# PCB-ACMSL.net
KiCad netlist of a schematic drawn in EAGLE
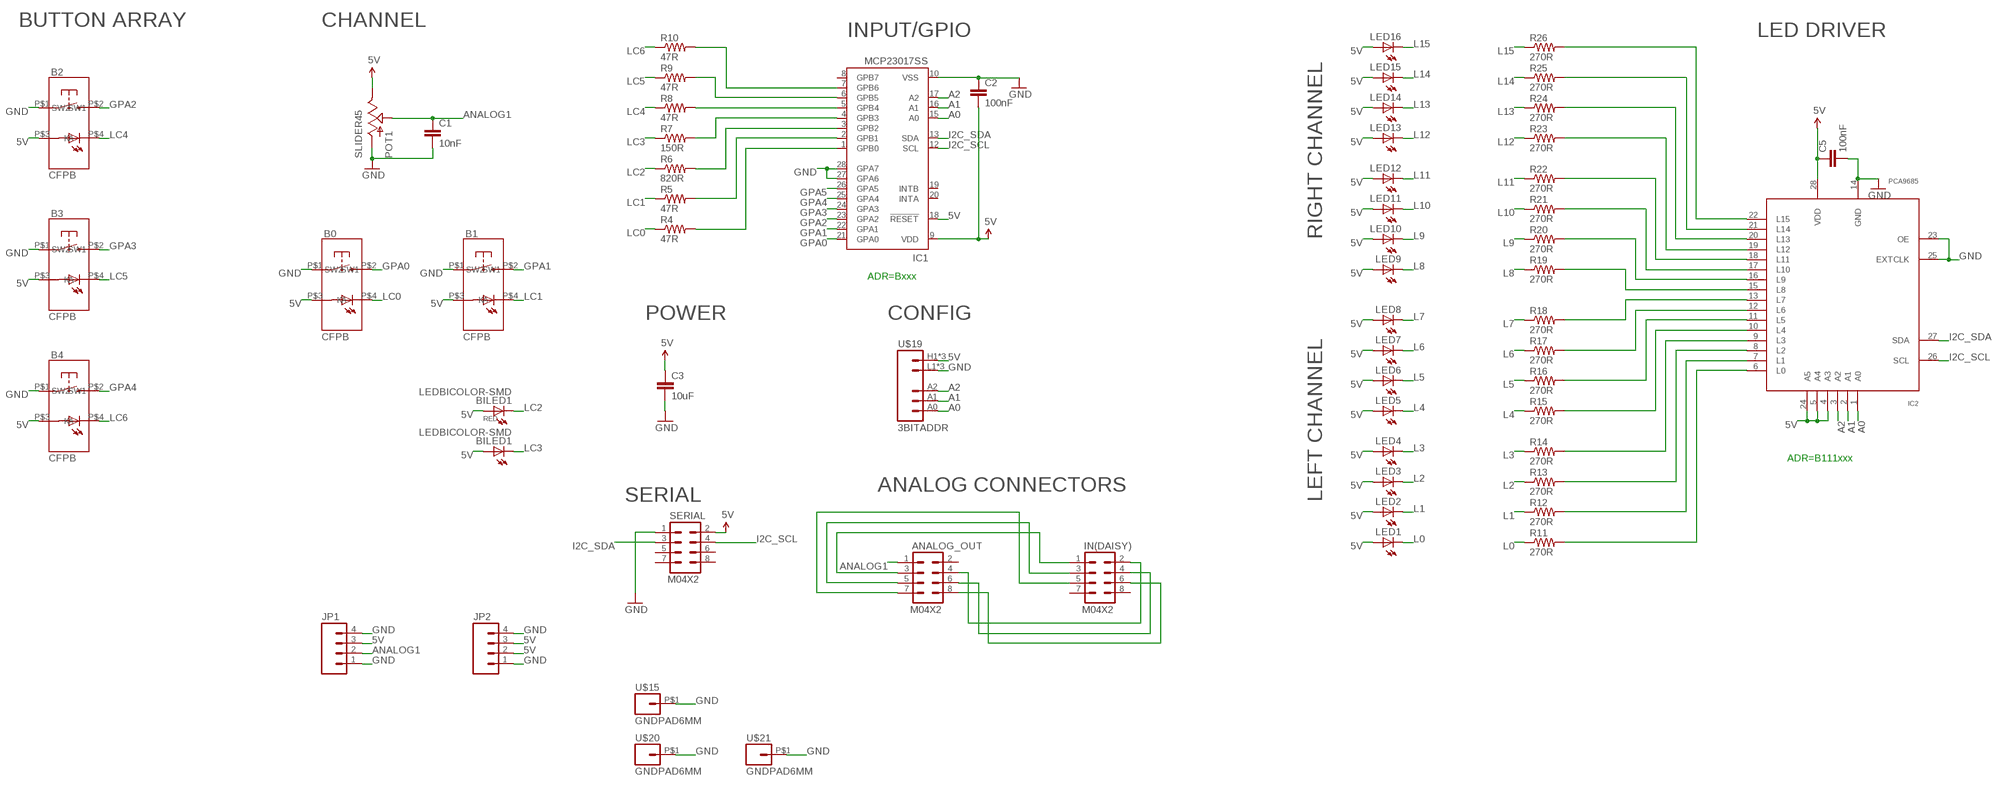
[diagram p0: schematic, sheet 1]

(export (version "E")
  (design (tool "Eeschema 10.0.6"))
  (components
    (comp (ref "ANALOG_OUT")
      (value "M04X2")
      (footprint "eagle-import:2X4")
      (libsource (lib "eagle-import") (part "M04X2"))
    )
    (comp (ref "B0")
      (value "CFPB")
      (footprint "eagle-import:CFPB-6_9MM")
      (libsource (lib "eagle-import") (part "CFPB"))
    )
    (comp (ref "B1")
      (value "CFPB")
      (footprint "eagle-import:CFPB-6_9MM")
      (libsource (lib "eagle-import") (part "CFPB"))
    )
    (comp (ref "B2")
      (value "CFPB")
      (footprint "eagle-import:CFPB-6_9MM")
      (libsource (lib "eagle-import") (part "CFPB"))
    )
    (comp (ref "B3")
      (value "CFPB")
      (footprint "eagle-import:CFPB-6_9MM")
      (libsource (lib "eagle-import") (part "CFPB"))
    )
    (comp (ref "B4")
      (value "CFPB")
      (footprint "eagle-import:CFPB-6_9MM")
      (libsource (lib "eagle-import") (part "CFPB"))
    )
    (comp (ref "BILED1")
      (value "LEDBICOLOR-SMD")
      (footprint "eagle-import:LEDBICOLOR-SMD")
      (libsource (lib "eagle-import") (part "LEDBICOLOR-SMD"))
    )
    (comp (ref "C1")
      (value "10nF")
      (footprint "eagle-import:0603-CAP")
      (libsource (lib "eagle-import") (part "CAP0603-CAP"))
    )
    (comp (ref "C2")
      (value "100nF")
      (footprint "eagle-import:0603-CAP")
      (libsource (lib "eagle-import") (part "CAP0603-CAP"))
    )
    (comp (ref "C3")
      (value "10uF")
      (footprint "eagle-import:0805")
      (libsource (lib "eagle-import") (part "CAP0805"))
    )
    (comp (ref "C5")
      (value "100nF")
      (footprint "eagle-import:0603-CAP")
      (libsource (lib "eagle-import") (part "CAP0603-CAP"))
    )
    (comp (ref "IC1")
      (value "MCP23017SS")
      (footprint "eagle-import:SSOP28")
      (fields
        (field (name "MF") "MICROCHIP")
        (field (name "MPN") "MCP23017-E/SS")
        (field (name "MPN_1") "MCP23017-E/SS")
        (field (name "OC_FARNELL") "1467674")
        (field (name "OC_NEWARK") "31K2960")
      )
      (libsource (lib "eagle-import") (part "MCP23017SS"))
    )
    (comp (ref "IC2")
      (value "PCA9685")
      (footprint "eagle-import:TSSOP28")
      (libsource (lib "eagle-import") (part "PCA9685"))
    )
    (comp (ref "IN(DAISY)")
      (value "M04X2")
      (footprint "eagle-import:2X4")
      (libsource (lib "eagle-import") (part "M04X2"))
    )
    (comp (ref "JP1")
      (value "M04PTH")
      (footprint "eagle-import:1X04")
      (libsource (lib "eagle-import") (part "M04PTH"))
    )
    (comp (ref "JP2")
      (value "M04PTH")
      (footprint "eagle-import:1X04")
      (libsource (lib "eagle-import") (part "M04PTH"))
    )
    (comp (ref "LED1")
      (value "LED3MM")
      (footprint "eagle-import:LED3MM")
      (libsource (lib "eagle-import") (part "LED3MM"))
    )
    (comp (ref "LED2")
      (value "LED3MM")
      (footprint "eagle-import:LED3MM")
      (libsource (lib "eagle-import") (part "LED3MM"))
    )
    (comp (ref "LED3")
      (value "LED3MM")
      (footprint "eagle-import:LED3MM")
      (libsource (lib "eagle-import") (part "LED3MM"))
    )
    (comp (ref "LED4")
      (value "LED3MM")
      (footprint "eagle-import:LED3MM")
      (libsource (lib "eagle-import") (part "LED3MM"))
    )
    (comp (ref "LED5")
      (value "LED3MM")
      (footprint "eagle-import:LED3MM")
      (libsource (lib "eagle-import") (part "LED3MM"))
    )
    (comp (ref "LED6")
      (value "LED3MM")
      (footprint "eagle-import:LED3MM")
      (libsource (lib "eagle-import") (part "LED3MM"))
    )
    (comp (ref "LED7")
      (value "LED3MM")
      (footprint "eagle-import:LED3MM")
      (libsource (lib "eagle-import") (part "LED3MM"))
    )
    (comp (ref "LED8")
      (value "LED3MM")
      (footprint "eagle-import:LED3MM")
      (libsource (lib "eagle-import") (part "LED3MM"))
    )
    (comp (ref "LED9")
      (value "LED3MM")
      (footprint "eagle-import:LED3MM")
      (libsource (lib "eagle-import") (part "LED3MM"))
    )
    (comp (ref "LED10")
      (value "LED3MM")
      (footprint "eagle-import:LED3MM")
      (libsource (lib "eagle-import") (part "LED3MM"))
    )
    (comp (ref "LED11")
      (value "LED3MM")
      (footprint "eagle-import:LED3MM")
      (libsource (lib "eagle-import") (part "LED3MM"))
    )
    (comp (ref "LED12")
      (value "LED3MM")
      (footprint "eagle-import:LED3MM")
      (libsource (lib "eagle-import") (part "LED3MM"))
    )
    (comp (ref "LED13")
      (value "LED3MM")
      (footprint "eagle-import:LED3MM")
      (libsource (lib "eagle-import") (part "LED3MM"))
    )
    (comp (ref "LED14")
      (value "LED3MM")
      (footprint "eagle-import:LED3MM")
      (libsource (lib "eagle-import") (part "LED3MM"))
    )
    (comp (ref "LED15")
      (value "LED3MM")
      (footprint "eagle-import:LED3MM")
      (libsource (lib "eagle-import") (part "LED3MM"))
    )
    (comp (ref "LED16")
      (value "LED3MM")
      (footprint "eagle-import:LED3MM")
      (libsource (lib "eagle-import") (part "LED3MM"))
    )
    (comp (ref "POT1")
      (value "SLIDER45")
      (footprint "eagle-import:SLIDER45")
      (libsource (lib "eagle-import") (part "SLIDER45"))
    )
    (comp (ref "R4")
      (value "47R")
      (footprint "eagle-import:0603-RES")
      (libsource (lib "eagle-import") (part "RESISTOR0603-RES"))
    )
    (comp (ref "R5")
      (value "47R")
      (footprint "eagle-import:0603-RES")
      (libsource (lib "eagle-import") (part "RESISTOR0603-RES"))
    )
    (comp (ref "R6")
      (value "820R")
      (footprint "eagle-import:0603-RES")
      (libsource (lib "eagle-import") (part "RESISTOR0603-RES"))
    )
    (comp (ref "R7")
      (value "150R")
      (footprint "eagle-import:0603-RES")
      (libsource (lib "eagle-import") (part "RESISTOR0603-RES"))
    )
    (comp (ref "R8")
      (value "47R")
      (footprint "eagle-import:0603-RES")
      (libsource (lib "eagle-import") (part "RESISTOR0603-RES"))
    )
    (comp (ref "R9")
      (value "47R")
      (footprint "eagle-import:0603-RES")
      (libsource (lib "eagle-import") (part "RESISTOR0603-RES"))
    )
    (comp (ref "R10")
      (value "47R")
      (footprint "eagle-import:0603-RES")
      (libsource (lib "eagle-import") (part "RESISTOR0603-RES"))
    )
    (comp (ref "R11")
      (value "270R")
      (footprint "eagle-import:0603-RES")
      (libsource (lib "eagle-import") (part "RESISTOR0603-RES"))
    )
    (comp (ref "R12")
      (value "270R")
      (footprint "eagle-import:0603-RES")
      (libsource (lib "eagle-import") (part "RESISTOR0603-RES"))
    )
    (comp (ref "R13")
      (value "270R")
      (footprint "eagle-import:0603-RES")
      (libsource (lib "eagle-import") (part "RESISTOR0603-RES"))
    )
    (comp (ref "R14")
      (value "270R")
      (footprint "eagle-import:0603-RES")
      (libsource (lib "eagle-import") (part "RESISTOR0603-RES"))
    )
    (comp (ref "R15")
      (value "270R")
      (footprint "eagle-import:0603-RES")
      (libsource (lib "eagle-import") (part "RESISTOR0603-RES"))
    )
    (comp (ref "R16")
      (value "270R")
      (footprint "eagle-import:0603-RES")
      (libsource (lib "eagle-import") (part "RESISTOR0603-RES"))
    )
    (comp (ref "R17")
      (value "270R")
      (footprint "eagle-import:0603-RES")
      (libsource (lib "eagle-import") (part "RESISTOR0603-RES"))
    )
    (comp (ref "R18")
      (value "270R")
      (footprint "eagle-import:0603-RES")
      (libsource (lib "eagle-import") (part "RESISTOR0603-RES"))
    )
    (comp (ref "R19")
      (value "270R")
      (footprint "eagle-import:0603-RES")
      (libsource (lib "eagle-import") (part "RESISTOR0603-RES"))
    )
    (comp (ref "R20")
      (value "270R")
      (footprint "eagle-import:0603-RES")
      (libsource (lib "eagle-import") (part "RESISTOR0603-RES"))
    )
    (comp (ref "R21")
      (value "270R")
      (footprint "eagle-import:0603-RES")
      (libsource (lib "eagle-import") (part "RESISTOR0603-RES"))
    )
    (comp (ref "R22")
      (value "270R")
      (footprint "eagle-import:0603-RES")
      (libsource (lib "eagle-import") (part "RESISTOR0603-RES"))
    )
    (comp (ref "R23")
      (value "270R")
      (footprint "eagle-import:0603-RES")
      (libsource (lib "eagle-import") (part "RESISTOR0603-RES"))
    )
    (comp (ref "R24")
      (value "270R")
      (footprint "eagle-import:0603-RES")
      (libsource (lib "eagle-import") (part "RESISTOR0603-RES"))
    )
    (comp (ref "R25")
      (value "270R")
      (footprint "eagle-import:0603-RES")
      (libsource (lib "eagle-import") (part "RESISTOR0603-RES"))
    )
    (comp (ref "R26")
      (value "270R")
      (footprint "eagle-import:0603-RES")
      (libsource (lib "eagle-import") (part "RESISTOR0603-RES"))
    )
    (comp (ref "SERIAL")
      (value "M04X2")
      (footprint "eagle-import:2X4")
      (libsource (lib "eagle-import") (part "M04X2"))
    )
    (comp (ref "U$15")
      (value "GNDPAD6MM")
      (footprint "eagle-import:3.2MMPAD6MM")
      (libsource (lib "eagle-import") (part "GNDPAD6MM"))
    )
    (comp (ref "U$19")
      (value "3BITADDR")
      (footprint "eagle-import:3BITADDR")
      (libsource (lib "eagle-import") (part "3BITADDR"))
    )
    (comp (ref "U$20")
      (value "GNDPAD6MM")
      (footprint "eagle-import:3.2MMPAD6MM")
      (libsource (lib "eagle-import") (part "GNDPAD6MM"))
    )
    (comp (ref "U$21")
      (value "GNDPAD6MM")
      (footprint "eagle-import:3.2MMPAD6MM")
      (libsource (lib "eagle-import") (part "GNDPAD6MM"))
    )
  )
  (nets
    (net (code "1") (name "/A0") (class "Default")
      (node (ref "IC1") (pin "15") (pinfunction "A0_15") (pintype "input"))
      (node (ref "IC2") (pin "1") (pinfunction "A0_1") (pintype "input"))
      (node (ref "U$19") (pin "A0") (pinfunction "A0_A0") (pintype "passive"))
    )
    (net (code "2") (name "/A1") (class "Default")
      (node (ref "IC1") (pin "16") (pinfunction "A1_16") (pintype "input"))
      (node (ref "IC2") (pin "2") (pinfunction "A1_2") (pintype "input"))
      (node (ref "U$19") (pin "A1") (pinfunction "A1_A1") (pintype "passive"))
    )
    (net (code "3") (name "/A2") (class "Default")
      (node (ref "IC1") (pin "17") (pinfunction "A2_17") (pintype "input"))
      (node (ref "IC2") (pin "3") (pinfunction "A2_3") (pintype "input"))
      (node (ref "U$19") (pin "A2") (pinfunction "A2_A2") (pintype "passive"))
    )
    (net (code "4") (name "/ANALOG1") (class "Default")
      (node (ref "ANALOG_OUT") (pin "1") (pinfunction "1_1") (pintype "passive"))
      (node (ref "C1") (pin "1") (pinfunction "1_1") (pintype "passive"))
      (node (ref "JP1") (pin "2") (pinfunction "2_2") (pintype "passive"))
      (node (ref "POT1") (pin "2A") (pinfunction "S_2A") (pintype "passive"))
    )
    (net (code "5") (name "/GPA0") (class "Default")
      (node (ref "B0") (pin "P$2") (pinfunction "SW2_P$2") (pintype "bidirectional"))
      (node (ref "IC1") (pin "21") (pinfunction "GPA0_21") (pintype "bidirectional"))
    )
    (net (code "6") (name "/GPA1") (class "Default")
      (node (ref "B1") (pin "P$2") (pinfunction "SW2_P$2") (pintype "bidirectional"))
      (node (ref "IC1") (pin "22") (pinfunction "GPA1_22") (pintype "bidirectional"))
    )
    (net (code "7") (name "/GPA2") (class "Default")
      (node (ref "B2") (pin "P$2") (pinfunction "SW2_P$2") (pintype "bidirectional"))
      (node (ref "IC1") (pin "23") (pinfunction "GPA2_23") (pintype "bidirectional"))
    )
    (net (code "8") (name "/GPA3") (class "Default")
      (node (ref "B3") (pin "P$2") (pinfunction "SW2_P$2") (pintype "bidirectional"))
      (node (ref "IC1") (pin "24") (pinfunction "GPA3_24") (pintype "bidirectional"))
    )
    (net (code "9") (name "/GPA4") (class "Default")
      (node (ref "B4") (pin "P$2") (pinfunction "SW2_P$2") (pintype "bidirectional"))
      (node (ref "IC1") (pin "25") (pinfunction "GPA4_25") (pintype "bidirectional"))
    )
    (net (code "10") (name "/GPA5") (class "Default")
      (node (ref "IC1") (pin "26") (pinfunction "GPA5_26") (pintype "bidirectional"))
    )
    (net (code "11") (name "/I2C_SCL") (class "Default")
      (node (ref "IC1") (pin "12") (pinfunction "SCL_12") (pintype "input"))
      (node (ref "IC2") (pin "26") (pinfunction "SCL_26") (pintype "input"))
      (node (ref "SERIAL") (pin "4") (pinfunction "4_4") (pintype "passive"))
    )
    (net (code "12") (name "/I2C_SDA") (class "Default")
      (node (ref "IC1") (pin "13") (pinfunction "SDA_13") (pintype "bidirectional"))
      (node (ref "IC2") (pin "27") (pinfunction "SDA_27") (pintype "input"))
      (node (ref "SERIAL") (pin "3") (pinfunction "3_3") (pintype "passive"))
    )
    (net (code "13") (name "/L0") (class "Default")
      (node (ref "LED1") (pin "K") (pinfunction "C_K") (pintype "passive"))
      (node (ref "R11") (pin "1") (pinfunction "1_1") (pintype "passive"))
    )
    (net (code "14") (name "/L1") (class "Default")
      (node (ref "LED2") (pin "K") (pinfunction "C_K") (pintype "passive"))
      (node (ref "R12") (pin "1") (pinfunction "1_1") (pintype "passive"))
    )
    (net (code "15") (name "/L2") (class "Default")
      (node (ref "LED3") (pin "K") (pinfunction "C_K") (pintype "passive"))
      (node (ref "R13") (pin "1") (pinfunction "1_1") (pintype "passive"))
    )
    (net (code "16") (name "/L3") (class "Default")
      (node (ref "LED4") (pin "K") (pinfunction "C_K") (pintype "passive"))
      (node (ref "R14") (pin "1") (pinfunction "1_1") (pintype "passive"))
    )
    (net (code "17") (name "/L4") (class "Default")
      (node (ref "LED5") (pin "K") (pinfunction "C_K") (pintype "passive"))
      (node (ref "R15") (pin "1") (pinfunction "1_1") (pintype "passive"))
    )
    (net (code "18") (name "/L5") (class "Default")
      (node (ref "LED6") (pin "K") (pinfunction "C_K") (pintype "passive"))
      (node (ref "R16") (pin "1") (pinfunction "1_1") (pintype "passive"))
    )
    (net (code "19") (name "/L6") (class "Default")
      (node (ref "LED7") (pin "K") (pinfunction "C_K") (pintype "passive"))
      (node (ref "R17") (pin "1") (pinfunction "1_1") (pintype "passive"))
    )
    (net (code "20") (name "/L7") (class "Default")
      (node (ref "LED8") (pin "K") (pinfunction "C_K") (pintype "passive"))
      (node (ref "R18") (pin "1") (pinfunction "1_1") (pintype "passive"))
    )
    (net (code "21") (name "/L8") (class "Default")
      (node (ref "LED9") (pin "K") (pinfunction "C_K") (pintype "passive"))
      (node (ref "R19") (pin "1") (pinfunction "1_1") (pintype "passive"))
    )
    (net (code "22") (name "/L9") (class "Default")
      (node (ref "LED10") (pin "K") (pinfunction "C_K") (pintype "passive"))
      (node (ref "R20") (pin "1") (pinfunction "1_1") (pintype "passive"))
    )
    (net (code "23") (name "/L10") (class "Default")
      (node (ref "LED11") (pin "K") (pinfunction "C_K") (pintype "passive"))
      (node (ref "R21") (pin "1") (pinfunction "1_1") (pintype "passive"))
    )
    (net (code "24") (name "/L11") (class "Default")
      (node (ref "LED12") (pin "K") (pinfunction "C_K") (pintype "passive"))
      (node (ref "R22") (pin "1") (pinfunction "1_1") (pintype "passive"))
    )
    (net (code "25") (name "/L12") (class "Default")
      (node (ref "LED13") (pin "K") (pinfunction "C_K") (pintype "passive"))
      (node (ref "R23") (pin "1") (pinfunction "1_1") (pintype "passive"))
    )
    (net (code "26") (name "/L13") (class "Default")
      (node (ref "LED14") (pin "K") (pinfunction "C_K") (pintype "passive"))
      (node (ref "R24") (pin "1") (pinfunction "1_1") (pintype "passive"))
    )
    (net (code "27") (name "/L14") (class "Default")
      (node (ref "LED15") (pin "K") (pinfunction "C_K") (pintype "passive"))
      (node (ref "R25") (pin "1") (pinfunction "1_1") (pintype "passive"))
    )
    (net (code "28") (name "/L15") (class "Default")
      (node (ref "LED16") (pin "K") (pinfunction "C_K") (pintype "passive"))
      (node (ref "R26") (pin "1") (pinfunction "1_1") (pintype "passive"))
    )
    (net (code "29") (name "/LC0") (class "Default")
      (node (ref "B0") (pin "P$4") (pinfunction "K_P$4") (pintype "bidirectional"))
      (node (ref "R4") (pin "1") (pinfunction "1_1") (pintype "passive"))
    )
    (net (code "30") (name "/LC1") (class "Default")
      (node (ref "B1") (pin "P$4") (pinfunction "K_P$4") (pintype "bidirectional"))
      (node (ref "R5") (pin "1") (pinfunction "1_1") (pintype "passive"))
    )
    (net (code "31") (name "/LC2") (class "Default")
      (node (ref "BILED1") (pin "P$2") (pinfunction "C_P$2") (pintype "passive"))
      (node (ref "R6") (pin "1") (pinfunction "1_1") (pintype "passive"))
    )
    (net (code "32") (name "/LC3") (class "Default")
      (node (ref "BILED1") (pin "P$4") (pinfunction "C1_P$4") (pintype "passive"))
      (node (ref "R7") (pin "1") (pinfunction "1_1") (pintype "passive"))
    )
    (net (code "33") (name "/LC4") (class "Default")
      (node (ref "B2") (pin "P$4") (pinfunction "K_P$4") (pintype "bidirectional"))
      (node (ref "R8") (pin "1") (pinfunction "1_1") (pintype "passive"))
    )
    (net (code "34") (name "/LC5") (class "Default")
      (node (ref "B3") (pin "P$4") (pinfunction "K_P$4") (pintype "bidirectional"))
      (node (ref "R9") (pin "1") (pinfunction "1_1") (pintype "passive"))
    )
    (net (code "35") (name "/LC6") (class "Default")
      (node (ref "B4") (pin "P$4") (pinfunction "K_P$4") (pintype "bidirectional"))
      (node (ref "R10") (pin "1") (pinfunction "1_1") (pintype "passive"))
    )
    (net (code "36") (name "5V") (class "Default")
      (node (ref "B0") (pin "P$3") (pinfunction "A_P$3") (pintype "bidirectional"))
      (node (ref "B1") (pin "P$3") (pinfunction "A_P$3") (pintype "bidirectional"))
      (node (ref "B2") (pin "P$3") (pinfunction "A_P$3") (pintype "bidirectional"))
      (node (ref "B3") (pin "P$3") (pinfunction "A_P$3") (pintype "bidirectional"))
      (node (ref "B4") (pin "P$3") (pinfunction "A_P$3") (pintype "bidirectional"))
      (node (ref "BILED1") (pin "P$1") (pinfunction "A_P$1") (pintype "passive"))
      (node (ref "BILED1") (pin "P$3") (pinfunction "A1_P$3") (pintype "passive"))
      (node (ref "C2") (pin "2") (pinfunction "2_2") (pintype "passive"))
      (node (ref "C3") (pin "1") (pinfunction "1_1") (pintype "passive"))
      (node (ref "C5") (pin "1") (pinfunction "1_1") (pintype "passive"))
      (node (ref "IC1") (pin "18") (pinfunction "~{RESET}_18") (pintype "input"))
      (node (ref "IC1") (pin "9") (pinfunction "VDD_9") (pintype "power_in"))
      (node (ref "IC2") (pin "24") (pinfunction "A5_24") (pintype "input"))
      (node (ref "IC2") (pin "28") (pinfunction "VDD_28") (pintype "power_in"))
      (node (ref "IC2") (pin "4") (pinfunction "A3_4") (pintype "input"))
      (node (ref "IC2") (pin "5") (pinfunction "A4_5") (pintype "input"))
      (node (ref "JP1") (pin "3") (pinfunction "3_3") (pintype "passive"))
      (node (ref "JP2") (pin "2") (pinfunction "2_2") (pintype "passive"))
      (node (ref "JP2") (pin "3") (pinfunction "3_3") (pintype "passive"))
      (node (ref "LED1") (pin "A") (pinfunction "A_A") (pintype "passive"))
      (node (ref "LED10") (pin "A") (pinfunction "A_A") (pintype "passive"))
      (node (ref "LED11") (pin "A") (pinfunction "A_A") (pintype "passive"))
      (node (ref "LED12") (pin "A") (pinfunction "A_A") (pintype "passive"))
      (node (ref "LED13") (pin "A") (pinfunction "A_A") (pintype "passive"))
      (node (ref "LED14") (pin "A") (pinfunction "A_A") (pintype "passive"))
      (node (ref "LED15") (pin "A") (pinfunction "A_A") (pintype "passive"))
      (node (ref "LED16") (pin "A") (pinfunction "A_A") (pintype "passive"))
      (node (ref "LED2") (pin "A") (pinfunction "A_A") (pintype "passive"))
      (node (ref "LED3") (pin "A") (pinfunction "A_A") (pintype "passive"))
      (node (ref "LED4") (pin "A") (pinfunction "A_A") (pintype "passive"))
      (node (ref "LED5") (pin "A") (pinfunction "A_A") (pintype "passive"))
      (node (ref "LED6") (pin "A") (pinfunction "A_A") (pintype "passive"))
      (node (ref "LED7") (pin "A") (pinfunction "A_A") (pintype "passive"))
      (node (ref "LED8") (pin "A") (pinfunction "A_A") (pintype "passive"))
      (node (ref "LED9") (pin "A") (pinfunction "A_A") (pintype "passive"))
      (node (ref "POT1") (pin "1") (pinfunction "E_1") (pintype "passive"))
      (node (ref "SERIAL") (pin "2") (pinfunction "2_2") (pintype "passive"))
      (node (ref "U$19") (pin "H1") (pinfunction "VCC_H1") (pintype "passive"))
      (node (ref "U$19") (pin "H2") (pinfunction "VCC_H2") (pintype "passive"))
      (node (ref "U$19") (pin "H3") (pinfunction "VCC_H3") (pintype "passive"))
    )
    (net (code "37") (name "GND") (class "Default")
      (node (ref "B0") (pin "P$1") (pinfunction "SW1_P$1") (pintype "bidirectional"))
      (node (ref "B1") (pin "P$1") (pinfunction "SW1_P$1") (pintype "bidirectional"))
      (node (ref "B2") (pin "P$1") (pinfunction "SW1_P$1") (pintype "bidirectional"))
      (node (ref "B3") (pin "P$1") (pinfunction "SW1_P$1") (pintype "bidirectional"))
      (node (ref "B4") (pin "P$1") (pinfunction "SW1_P$1") (pintype "bidirectional"))
      (node (ref "C1") (pin "2") (pinfunction "2_2") (pintype "passive"))
      (node (ref "C2") (pin "1") (pinfunction "1_1") (pintype "passive"))
      (node (ref "C3") (pin "2") (pinfunction "2_2") (pintype "passive"))
      (node (ref "C5") (pin "2") (pinfunction "2_2") (pintype "passive"))
      (node (ref "IC1") (pin "10") (pinfunction "VSS_10") (pintype "power_in"))
      (node (ref "IC1") (pin "27") (pinfunction "GPA6_27") (pintype "bidirectional"))
      (node (ref "IC1") (pin "28") (pinfunction "GPA7_28") (pintype "bidirectional"))
      (node (ref "IC2") (pin "14") (pinfunction "GND_14") (pintype "power_in"))
      (node (ref "IC2") (pin "23") (pinfunction "OE_23") (pintype "input"))
      (node (ref "IC2") (pin "25") (pinfunction "EXTCLK_25") (pintype "input"))
      (node (ref "JP1") (pin "1") (pinfunction "1_1") (pintype "passive"))
      (node (ref "JP1") (pin "4") (pinfunction "4_4") (pintype "passive"))
      (node (ref "JP2") (pin "1") (pinfunction "1_1") (pintype "passive"))
      (node (ref "JP2") (pin "4") (pinfunction "4_4") (pintype "passive"))
      (node (ref "POT1") (pin "3") (pinfunction "A_3") (pintype "passive"))
      (node (ref "SERIAL") (pin "1") (pinfunction "1_1") (pintype "passive"))
      (node (ref "U$15") (pin "P$1") (pinfunction "1_P$1") (pintype "passive"))
      (node (ref "U$19") (pin "L1") (pinfunction "GND_L1") (pintype "passive"))
      (node (ref "U$19") (pin "L2") (pinfunction "GND_L2") (pintype "passive"))
      (node (ref "U$19") (pin "L3") (pinfunction "GND_L3") (pintype "passive"))
      (node (ref "U$20") (pin "P$1") (pinfunction "1_P$1") (pintype "passive"))
      (node (ref "U$21") (pin "P$1") (pinfunction "1_P$1") (pintype "passive"))
    )
    (net (code "38") (name "Net-(ANALOG_OUT-Pad3)") (class "Default")
      (node (ref "ANALOG_OUT") (pin "3") (pinfunction "3_3") (pintype "passive"))
      (node (ref "IN(DAISY)") (pin "1") (pinfunction "1_1") (pintype "passive"))
    )
    (net (code "39") (name "Net-(ANALOG_OUT-Pad4)") (class "Default")
      (node (ref "ANALOG_OUT") (pin "4") (pinfunction "4_4") (pintype "passive"))
      (node (ref "IN(DAISY)") (pin "2") (pinfunction "2_2") (pintype "passive"))
    )
    (net (code "40") (name "Net-(ANALOG_OUT-Pad5)") (class "Default")
      (node (ref "ANALOG_OUT") (pin "5") (pinfunction "5_5") (pintype "passive"))
      (node (ref "IN(DAISY)") (pin "3") (pinfunction "3_3") (pintype "passive"))
    )
    (net (code "41") (name "Net-(ANALOG_OUT-Pad6)") (class "Default")
      (node (ref "ANALOG_OUT") (pin "6") (pinfunction "6_6") (pintype "passive"))
      (node (ref "IN(DAISY)") (pin "4") (pinfunction "4_4") (pintype "passive"))
    )
    (net (code "42") (name "Net-(ANALOG_OUT-Pad7)") (class "Default")
      (node (ref "ANALOG_OUT") (pin "7") (pinfunction "7_7") (pintype "passive"))
      (node (ref "IN(DAISY)") (pin "5") (pinfunction "5_5") (pintype "passive"))
    )
    (net (code "43") (name "Net-(ANALOG_OUT-Pad8)") (class "Default")
      (node (ref "ANALOG_OUT") (pin "8") (pinfunction "8_8") (pintype "passive"))
      (node (ref "IN(DAISY)") (pin "6") (pinfunction "6_6") (pintype "passive"))
    )
    (net (code "44") (name "Net-(IC1-GPB0)") (class "Default")
      (node (ref "IC1") (pin "1") (pinfunction "GPB0_1") (pintype "bidirectional"))
      (node (ref "R4") (pin "2") (pinfunction "2_2") (pintype "passive"))
    )
    (net (code "45") (name "Net-(IC1-GPB1)") (class "Default")
      (node (ref "IC1") (pin "2") (pinfunction "GPB1_2") (pintype "bidirectional"))
      (node (ref "R5") (pin "2") (pinfunction "2_2") (pintype "passive"))
    )
    (net (code "46") (name "Net-(IC1-GPB2)") (class "Default")
      (node (ref "IC1") (pin "3") (pinfunction "GPB2_3") (pintype "bidirectional"))
      (node (ref "R6") (pin "2") (pinfunction "2_2") (pintype "passive"))
    )
    (net (code "47") (name "Net-(IC1-GPB3)") (class "Default")
      (node (ref "IC1") (pin "4") (pinfunction "GPB3_4") (pintype "bidirectional"))
      (node (ref "R7") (pin "2") (pinfunction "2_2") (pintype "passive"))
    )
    (net (code "48") (name "Net-(IC1-GPB4)") (class "Default")
      (node (ref "IC1") (pin "5") (pinfunction "GPB4_5") (pintype "bidirectional"))
      (node (ref "R8") (pin "2") (pinfunction "2_2") (pintype "passive"))
    )
    (net (code "49") (name "Net-(IC1-GPB5)") (class "Default")
      (node (ref "IC1") (pin "6") (pinfunction "GPB5_6") (pintype "bidirectional"))
      (node (ref "R9") (pin "2") (pinfunction "2_2") (pintype "passive"))
    )
    (net (code "50") (name "Net-(IC1-GPB6)") (class "Default")
      (node (ref "IC1") (pin "7") (pinfunction "GPB6_7") (pintype "bidirectional"))
      (node (ref "R10") (pin "2") (pinfunction "2_2") (pintype "passive"))
    )
    (net (code "51") (name "Net-(IC2-L0)") (class "Default")
      (node (ref "IC2") (pin "6") (pinfunction "L0_6") (pintype "output"))
      (node (ref "R11") (pin "2") (pinfunction "2_2") (pintype "passive"))
    )
    (net (code "52") (name "Net-(IC2-L1)") (class "Default")
      (node (ref "IC2") (pin "7") (pinfunction "L1_7") (pintype "output"))
      (node (ref "R12") (pin "2") (pinfunction "2_2") (pintype "passive"))
    )
    (net (code "53") (name "Net-(IC2-L2)") (class "Default")
      (node (ref "IC2") (pin "8") (pinfunction "L2_8") (pintype "output"))
      (node (ref "R13") (pin "2") (pinfunction "2_2") (pintype "passive"))
    )
    (net (code "54") (name "Net-(IC2-L3)") (class "Default")
      (node (ref "IC2") (pin "9") (pinfunction "L3_9") (pintype "output"))
      (node (ref "R14") (pin "2") (pinfunction "2_2") (pintype "passive"))
    )
    (net (code "55") (name "Net-(IC2-L4)") (class "Default")
      (node (ref "IC2") (pin "10") (pinfunction "L4_10") (pintype "output"))
      (node (ref "R15") (pin "2") (pinfunction "2_2") (pintype "passive"))
    )
    (net (code "56") (name "Net-(IC2-L5)") (class "Default")
      (node (ref "IC2") (pin "11") (pinfunction "L5_11") (pintype "output"))
      (node (ref "R16") (pin "2") (pinfunction "2_2") (pintype "passive"))
    )
    (net (code "57") (name "Net-(IC2-L6)") (class "Default")
      (node (ref "IC2") (pin "12") (pinfunction "L6_12") (pintype "output"))
      (node (ref "R17") (pin "2") (pinfunction "2_2") (pintype "passive"))
    )
    (net (code "58") (name "Net-(IC2-L7)") (class "Default")
      (node (ref "IC2") (pin "13") (pinfunction "L7_13") (pintype "output"))
      (node (ref "R18") (pin "2") (pinfunction "2_2") (pintype "passive"))
    )
    (net (code "59") (name "Net-(IC2-L8)") (class "Default")
      (node (ref "IC2") (pin "15") (pinfunction "L8_15") (pintype "output"))
      (node (ref "R19") (pin "2") (pinfunction "2_2") (pintype "passive"))
    )
    (net (code "60") (name "Net-(IC2-L9)") (class "Default")
      (node (ref "IC2") (pin "16") (pinfunction "L9_16") (pintype "output"))
      (node (ref "R20") (pin "2") (pinfunction "2_2") (pintype "passive"))
    )
    (net (code "61") (name "Net-(IC2-L10)") (class "Default")
      (node (ref "IC2") (pin "17") (pinfunction "L10_17") (pintype "output"))
      (node (ref "R21") (pin "2") (pinfunction "2_2") (pintype "passive"))
    )
    (net (code "62") (name "Net-(IC2-L11)") (class "Default")
      (node (ref "IC2") (pin "18") (pinfunction "L11_18") (pintype "output"))
      (node (ref "R22") (pin "2") (pinfunction "2_2") (pintype "passive"))
    )
    (net (code "63") (name "Net-(IC2-L12)") (class "Default")
      (node (ref "IC2") (pin "19") (pinfunction "L12_19") (pintype "output"))
      (node (ref "R23") (pin "2") (pinfunction "2_2") (pintype "passive"))
    )
    (net (code "64") (name "Net-(IC2-L13)") (class "Default")
      (node (ref "IC2") (pin "20") (pinfunction "L13_20") (pintype "output"))
      (node (ref "R24") (pin "2") (pinfunction "2_2") (pintype "passive"))
    )
    (net (code "65") (name "Net-(IC2-L14)") (class "Default")
      (node (ref "IC2") (pin "21") (pinfunction "L14_21") (pintype "output"))
      (node (ref "R25") (pin "2") (pinfunction "2_2") (pintype "passive"))
    )
    (net (code "66") (name "Net-(IC2-L15)") (class "Default")
      (node (ref "IC2") (pin "22") (pinfunction "L15_22") (pintype "output"))
      (node (ref "R26") (pin "2") (pinfunction "2_2") (pintype "passive"))
    )
    (net (code "67") (name "unconnected-(ANALOG_OUT-Pad2)") (class "Default")
      (node (ref "ANALOG_OUT") (pin "2") (pinfunction "2_2") (pintype "passive"))
    )
    (net (code "68") (name "unconnected-(IC1-GPB7-Pad8)") (class "Default")
      (node (ref "IC1") (pin "8") (pinfunction "GPB7_8") (pintype "bidirectional"))
    )
    (net (code "69") (name "unconnected-(IC1-INTA-Pad20)") (class "Default")
      (node (ref "IC1") (pin "20") (pinfunction "INTA_20") (pintype "output"))
    )
    (net (code "70") (name "unconnected-(IC1-INTB-Pad19)") (class "Default")
      (node (ref "IC1") (pin "19") (pinfunction "INTB_19") (pintype "output"))
    )
    (net (code "71") (name "unconnected-(IN(DAISY)-Pad7)") (class "Default")
      (node (ref "IN(DAISY)") (pin "7") (pinfunction "7_7") (pintype "passive"))
    )
    (net (code "72") (name "unconnected-(IN(DAISY)-Pad8)") (class "Default")
      (node (ref "IN(DAISY)") (pin "8") (pinfunction "8_8") (pintype "passive"))
    )
    (net (code "73") (name "unconnected-(SERIAL-Pad5)") (class "Default")
      (node (ref "SERIAL") (pin "5") (pinfunction "5_5") (pintype "passive"))
    )
    (net (code "74") (name "unconnected-(SERIAL-Pad6)") (class "Default")
      (node (ref "SERIAL") (pin "6") (pinfunction "6_6") (pintype "passive"))
    )
    (net (code "75") (name "unconnected-(SERIAL-Pad7)") (class "Default")
      (node (ref "SERIAL") (pin "7") (pinfunction "7_7") (pintype "passive"))
    )
    (net (code "76") (name "unconnected-(SERIAL-Pad8)") (class "Default")
      (node (ref "SERIAL") (pin "8") (pinfunction "8_8") (pintype "passive"))
    )
  )
)
